# Power.net
KiCad netlist of a schematic drawn in Altium Designer
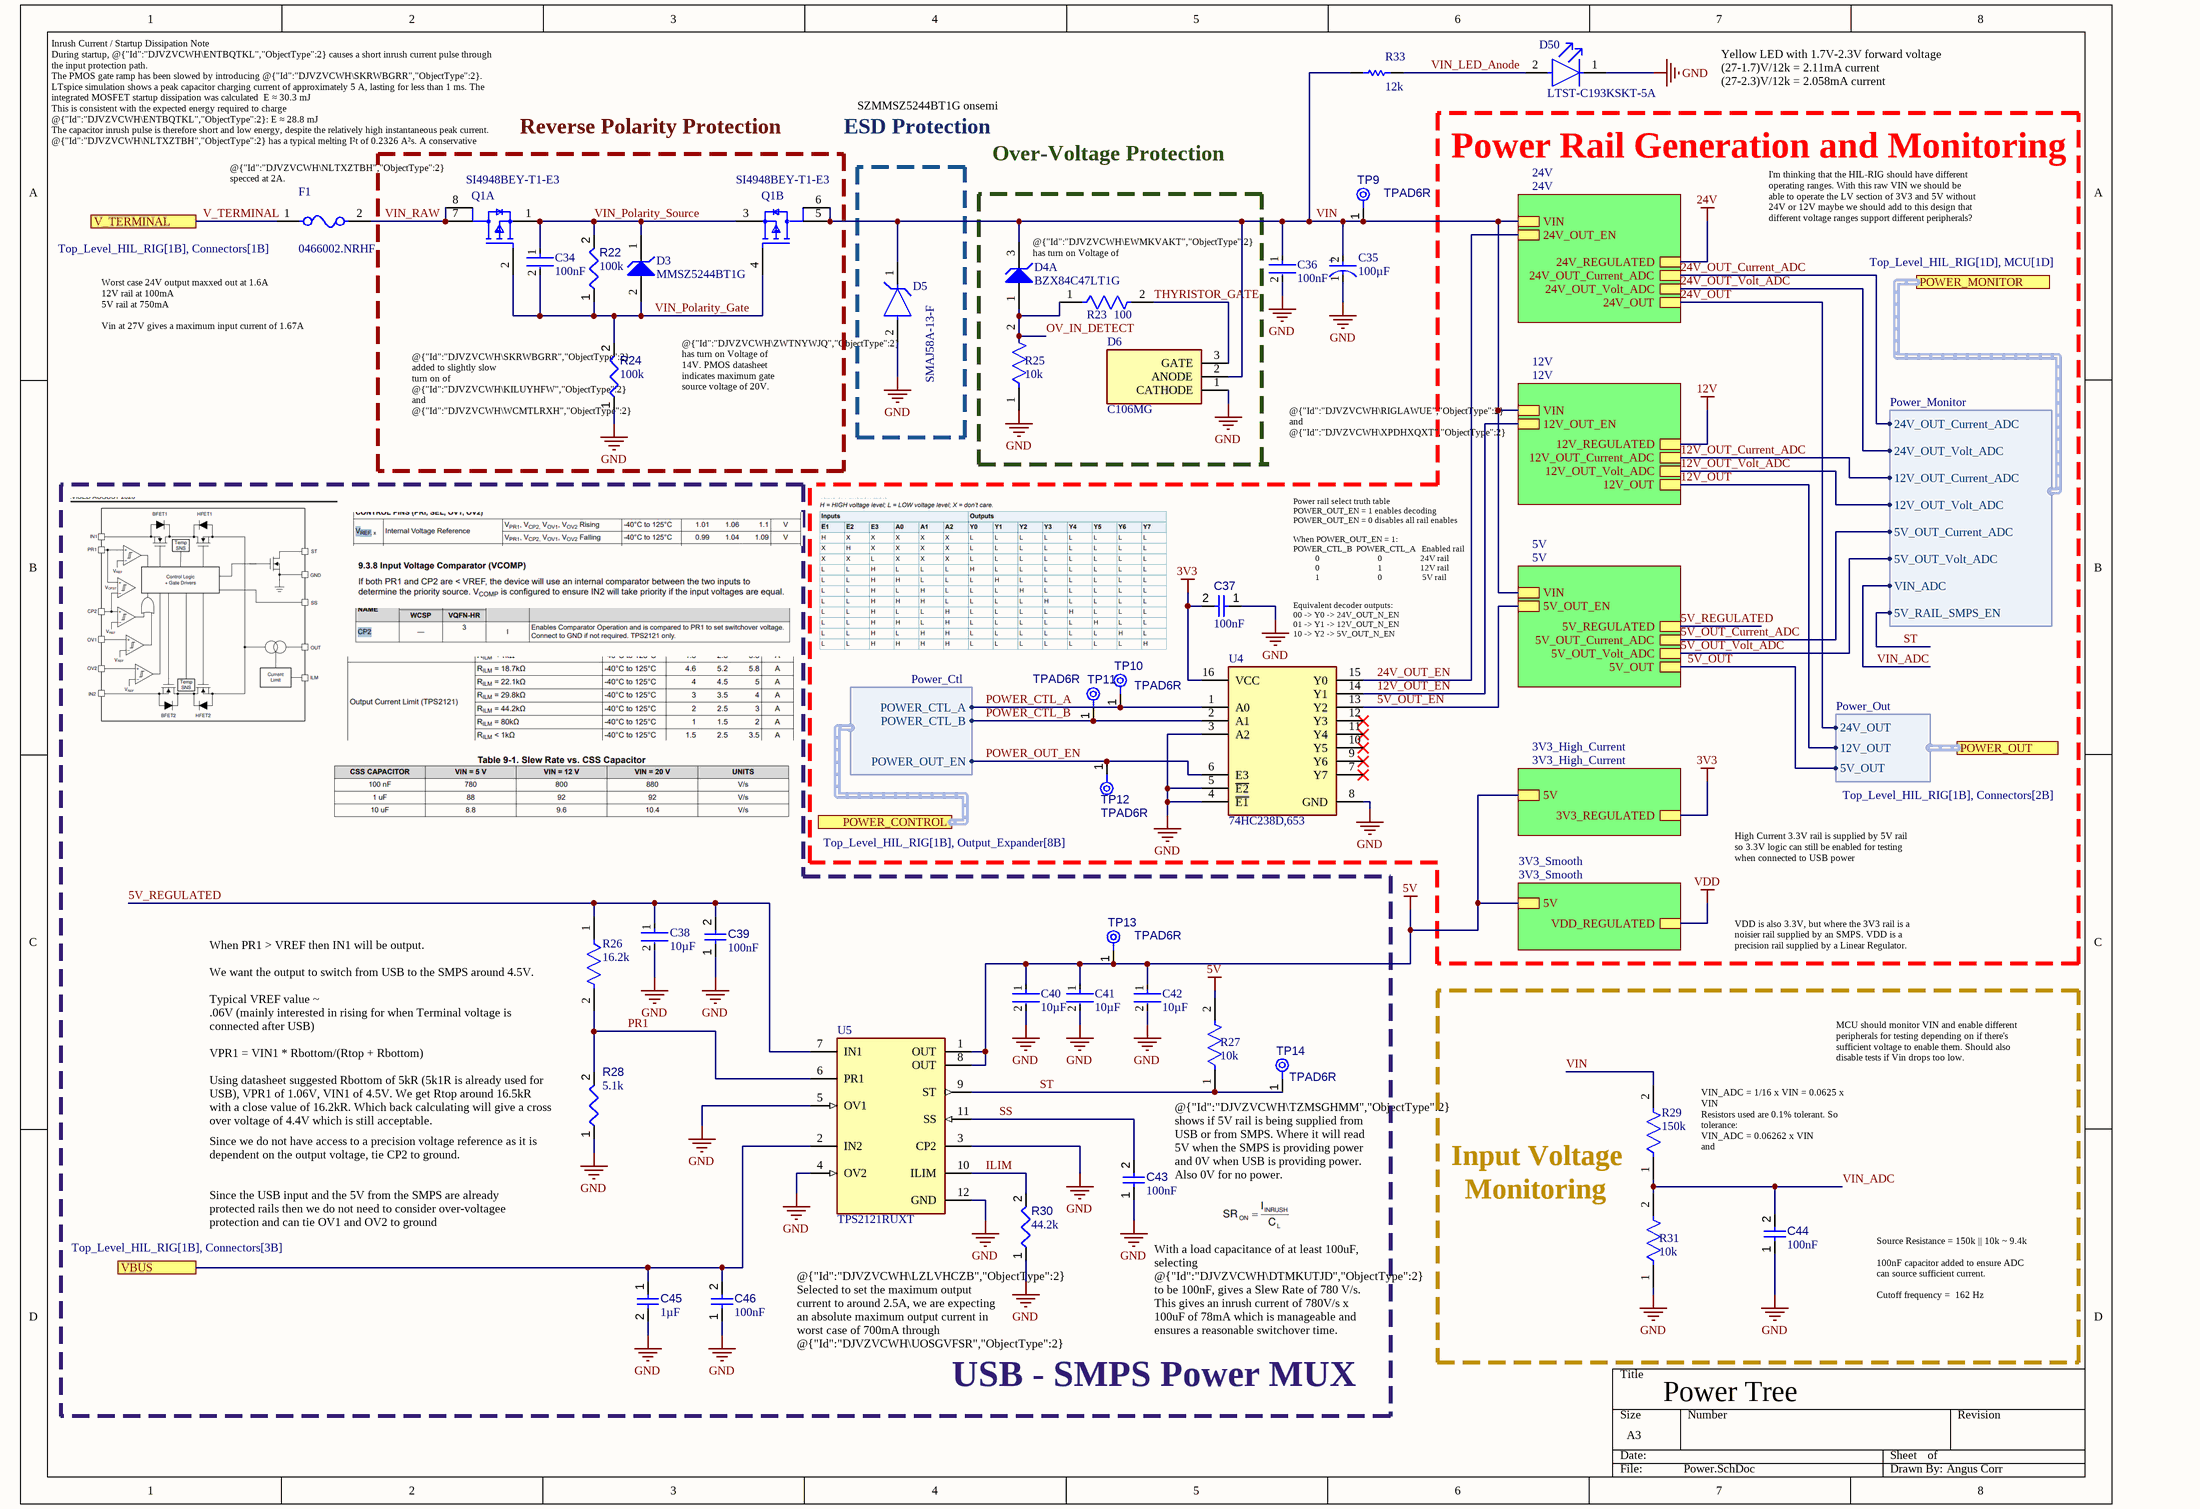
[diagram p0:  Power.SchDoc]

(export (version "E")
  (design (tool "Eeschema 10.0.6"))
  (components
    (comp (ref "C34")
      (value "100nF")
      (footprint "FP-GRM31C-0_2-e0_3_0_8-IPC_C")
      (description "100V 100nF C0G ±5% 1206 Multilayer Ceramic Capacitors MLCC - SMD/SMT ROHS")
      (fields (field (name "TOLERANCE") "5%") (field (name "Comment") "GRM31C5C2A104JA01L"))
      (libsource (lib "HIL RIG FYP") (part "02cd4be3c70576c341d710602a673aa"))
    )
    (comp (ref "C35")
      (value "100µF")
      (footprint "FP-MVYAKE0-MFG")
      (description "Cap Aluminum 100uF 100V 20% (12.5 X 13.5mm) SMD 450mA 5000h 105°C T/R")
      (fields (field (name "TOLERANCE") "20%") (field (name "Comment") "EMVY101ARA101MKE0S"))
      (libsource (lib "HIL RIG FYP") (part "203bc49f2ac43e59fd269a8c329ed05"))
    )
    (comp (ref "C36")
      (value "100nF")
      (footprint "FP-GRM31C-0_2-e0_3_0_8-IPC_C")
      (description "100V 100nF C0G ±5% 1206 Multilayer Ceramic Capacitors MLCC - SMD/SMT ROHS")
      (fields (field (name "TOLERANCE") "5%") (field (name "Comment") "GRM31C5C2A104JA01L"))
      (libsource (lib "HIL RIG FYP") (part "02cd4be3c70576c341d710602a673aa"))
    )
    (comp (ref "C37")
      (value "100nF")
      (footprint "CAPC1608X90X40NL10T20")
      (description "Chip Capacitor, 100 nF, +/- 10%, 50 V, 0603 (1608 Metric)")
      (fields (field (name "TOLERANCE") "10%") (field (name "Comment") "Capacitor 100 nF +/-10% 50 V 0603"))
      (libsource (lib "HIL RIG FYP") (part "CAP-NP-2"))
    )
    (comp (ref "C38")
      (value "10µF")
      (footprint "FP-GRM31C-0_2-e0_3_0_8-IPC_C")
      (description "25V 10uF X7R ±10% 1206 Multilayer Ceramic Capacitors MLCC - SMD/SMT ROHS")
      (fields (field (name "TOLERANCE") "10%") (field (name "VOLTAGE") "25V"))
      (libsource (lib "HIL RIG FYP") (part "02cd4be3c70576c341d710602a673aa"))
    )
    (comp (ref "C39")
      (value "100nF")
      (footprint "CAPC1608X90X40NL10T20")
      (description "Chip Capacitor, 100 nF, +/- 10%, 50 V, 0603 (1608 Metric)")
      (fields (field (name "TOLERANCE") "10%") (field (name "Comment") "Capacitor 100 nF +/-10% 50 V 0603"))
      (libsource (lib "HIL RIG FYP") (part "CAP-NP-2"))
    )
    (comp (ref "C40")
      (value "10µF")
      (footprint "FP-GRM31C-0_2-e0_3_0_8-IPC_C")
      (description "25V 10uF X7R ±10% 1206 Multilayer Ceramic Capacitors MLCC - SMD/SMT ROHS")
      (fields (field (name "TOLERANCE") "10%") (field (name "VOLTAGE") "25V"))
      (libsource (lib "HIL RIG FYP") (part "02cd4be3c70576c341d710602a673aa"))
    )
    (comp (ref "C41")
      (value "10µF")
      (footprint "FP-GRM31C-0_2-e0_3_0_8-IPC_C")
      (description "25V 10uF X7R ±10% 1206 Multilayer Ceramic Capacitors MLCC - SMD/SMT ROHS")
      (fields (field (name "TOLERANCE") "10%") (field (name "VOLTAGE") "25V"))
      (libsource (lib "HIL RIG FYP") (part "02cd4be3c70576c341d710602a673aa"))
    )
    (comp (ref "C42")
      (value "10µF")
      (footprint "FP-GRM31C-0_2-e0_3_0_8-IPC_C")
      (description "25V 10uF X7R ±10% 1206 Multilayer Ceramic Capacitors MLCC - SMD/SMT ROHS")
      (fields (field (name "TOLERANCE") "10%") (field (name "VOLTAGE") "25V"))
      (libsource (lib "HIL RIG FYP") (part "02cd4be3c70576c341d710602a673aa"))
    )
    (comp (ref "C43")
      (value "100nF")
      (footprint "CAPC1608X90X40NL10T20")
      (description "Chip Capacitor, 100 nF, +/- 10%, 50 V, 0603 (1608 Metric)")
      (fields (field (name "TOLERANCE") "10%") (field (name "Comment") "Capacitor 100 nF +/-10% 50 V 0603"))
      (libsource (lib "HIL RIG FYP") (part "CAP-NP-2"))
    )
    (comp (ref "C44")
      (value "100nF")
      (footprint "CAPC1608X90X40NL10T20")
      (description "Chip Capacitor, 100 nF, +/- 10%, 50 V, 0603 (1608 Metric)")
      (fields (field (name "TOLERANCE") "10%") (field (name "Comment") "Capacitor 100 nF +/-10% 50 V 0603"))
      (libsource (lib "HIL RIG FYP") (part "CAP-NP-2"))
    )
    (comp (ref "C45")
      (value "1µF")
      (footprint "CAPC1608X90X40LL10T20")
      (description "Chip Capacitor, 1 uF, +/- 10%, 25 V, 0603 (1608 Metric)")
      (fields (field (name "TOLERANCE") "10%") (field (name "Comment") "Capacitor 1 uF +/- 10% 25 V 0603"))
      (libsource (lib "HIL RIG FYP") (part "CAP-NP-2"))
    )
    (comp (ref "C46")
      (value "100nF")
      (footprint "CAPC1608X90X40NL10T20")
      (description "Chip Capacitor, 100 nF, +/- 10%, 50 V, 0603 (1608 Metric)")
      (fields (field (name "TOLERANCE") "10%") (field (name "Comment") "Capacitor 100 nF +/-10% 50 V 0603"))
      (libsource (lib "HIL RIG FYP") (part "CAP-NP-2"))
    )
    (comp (ref "D3")
      (value "MMSZ5244BT1G")
      (footprint "ONSC-SOD-123-2-425-04_V")
      (description "MMSZ5244BT1 Series 500 mW 10 mA 14 V SMT Zener Voltage Regulator - SOD-123")
      (fields (field (name "TOLERANCE") "5%"))
      (libsource (lib "HIL RIG FYP") (part "ONSC-K1A2-2"))
    )
    (comp (ref "D4")
      (value "BZX84C47LT1G")
      (footprint "ONSC-SOT-23-3-318-08_V")
      (description "Diode, Zener, Vr 47V, If 10MA, Pkg SOT-23 (TO-236), Vf 0.9V, Cj 40PF, Tj +150C, Ir 2MA")
      (libsource (lib "HIL RIG FYP") (part "ONSC-A1K3-3"))
    )
    (comp (ref "D5")
      (value "SMAJ58A-13-F")
      (footprint "FP-SMA-MFG")
      (description "SMAJ Series 58 V 400 W SMT Uni-Directional TVS Diode - DO-214AC")
      (libsource (lib "HIL RIG FYP") (part "f813f71cba58e380607f5dd3caf9714"))
    )
    (comp (ref "D6")
      (value "C106MG")
      (footprint "TO229P280X780X1410-3P")
      (description "Littelfuse")
      (fields (field (name "MOUSER PART NUMBER") "863-C106MG"))
      (libsource (lib "HIL RIG FYP") (part "C106MG"))
    )
    (comp (ref "D50")
      (value "LTST-C193KSKT-5A")
      (footprint "FP-LTST-C193KGKT-5A-MFG")
      (description "LED yellow 0603 wavelength 587~594.5nm light intensity 7.1~45mcd Front Mounting")
      (libsource (lib "HIL RIG FYP") (part "8706943c75ba83719d021d2fdc84c58"))
    )
    (comp (ref "F1")
      (value "0466002.NRHF")
      (footprint "FP-0466-MFG")
      (description "Fuse 63V Fa Halogen Free Slim 1206 2A/ T&r Rohs Compliant: Yes")
      (libsource (lib "HIL RIG FYP") (part "5bcf9b9f640e542cf0359d10258e979"))
    )
    (comp (ref "Q1")
      (value "SI4948BEY-T1-E3")
      (footprint "FP-C-06527-IPC_B")
      (description "Dual P-Channel 60 V 0.12 Ohms Surface Mount Power Mosfet - SOIC-8")
      (libsource (lib "HIL RIG FYP") (part "8dc75c867fb8938c255332086adbf49"))
    )
    (comp (ref "R22")
      (value "100k")
      (footprint "FP-AC0603-IPC_C")
      (description "Res Thick Film 0603 100K Ohm 1% 0.1W(1/10W) ±100ppm/C Pad SMD T/R Automotive")
      (fields (field (name "TOLERANCE") "1%") (field (name "Comment") "AC0603FR-07100KL"))
      (libsource (lib "HIL RIG FYP") (part "RES-2"))
    )
    (comp (ref "R23")
      (value "100")
      (footprint "FP-RT0603-IPC_C")
      (description "100mW Thin Film Resistor 75V ±25ppm/℃ ±0.1% 100Ω 0603 Chip Resistor - Surface Mount ROHS")
      (fields (field (name "TOLERANCE") "0.1%") (field (name "Comment") "RT0603BRD07100RL"))
      (libsource (lib "HIL RIG FYP") (part "1029c3af85768c4190bb7ad29bc67b5"))
    )
    (comp (ref "R24")
      (value "100k")
      (footprint "FP-AC0603-IPC_C")
      (description "Res Thick Film 0603 100K Ohm 1% 0.1W(1/10W) ±100ppm/C Pad SMD T/R Automotive")
      (fields (field (name "TOLERANCE") "1%") (field (name "Comment") "AC0603FR-07100KL"))
      (libsource (lib "HIL RIG FYP") (part "RES-2"))
    )
    (comp (ref "R25")
      (value "10k")
      (footprint "FP-RT0603-IPC_C")
      (description "Res Thin Film 0603 10K Ohm 0.1% 1/10W ¦25ppm/¦C SMD Paper T/R")
      (fields (field (name "TOLERANCE") "0.1%") (field (name "Comment") "RT0603BRD0710KL"))
      (libsource (lib "HIL RIG FYP") (part "1029c3af85768c4190bb7ad29bc67b5"))
    )
    (comp (ref "R26")
      (value "16.2k")
      (footprint "FP-RT0603-IPC_C")
      (description "100mW Thin Film Resistor ±25ppm/℃ ±0.1% 16.2kΩ 0603 Chip Resistor - Surface Mount ROHS")
      (fields (field (name "TOLERANCE") "0.1%") (field (name "Comment") "RT0603BRD0716K2L"))
      (libsource (lib "HIL RIG FYP") (part "1029c3af85768c4190bb7ad29bc67b5"))
    )
    (comp (ref "R27")
      (value "10k")
      (footprint "FP-RT0603-IPC_C")
      (description "Res Thin Film 0603 10K Ohm 0.1% 1/10W ¦25ppm/¦C SMD Paper T/R")
      (fields (field (name "TOLERANCE") "0.1%") (field (name "Comment") "RT0603BRD0710KL"))
      (libsource (lib "HIL RIG FYP") (part "1029c3af85768c4190bb7ad29bc67b5"))
    )
    (comp (ref "R28")
      (value "5.1k")
      (footprint "FP-AC0603-IPC_C")
      (description "Res Thick Film 0603 5.1K Ohm 1% 0.1W(1/10W) ±100ppm/C Pad SMD Automotive T/R")
      (fields (field (name "TOLERANCE") "1%") (field (name "Comment") "AC0603FR-075K1L"))
      (libsource (lib "HIL RIG FYP") (part "RES-2"))
    )
    (comp (ref "R29")
      (value "150k")
      (footprint "FP-RT0805-MFG")
      (description "125mW Thin Film Resistor 150V ±25ppm/℃ ±0.1% 150kΩ 0805 Chip Resistor - Surface Mount ROHS")
      (fields (field (name "TOLERANCE") "0.1%") (field (name "Comment") "RT0805BRD07150KL"))
      (libsource (lib "HIL RIG FYP") (part "1029c3af85768c4190bb7ad29bc67b5"))
    )
    (comp (ref "R30")
      (value "44.2k")
      (footprint "FP-AC0603-IPC_C")
      (description "Res Thick Film 0603 44.2K Ohm 1% 0.1W(1/10W) ±100ppm/C Pad SMD T/R Automotive AEC-Q200")
      (fields (field (name "TOLERANCE") "1%") (field (name "Comment") "AC0603FR-0744K2L"))
      (libsource (lib "HIL RIG FYP") (part "RES-2"))
    )
    (comp (ref "R31")
      (value "10k")
      (footprint "FP-RT0603-IPC_C")
      (description "Res Thin Film 0603 10K Ohm 0.1% 1/10W ¦25ppm/¦C SMD Paper T/R")
      (fields (field (name "TOLERANCE") "0.1%") (field (name "Comment") "RT0603BRD0710KL"))
      (libsource (lib "HIL RIG FYP") (part "1029c3af85768c4190bb7ad29bc67b5"))
    )
    (comp (ref "R33")
      (value "12k")
      (footprint "RESC1608X55X25LL10T15")
      (description "100mW Thick Film Resistors 75V ±100ppm/℃ ±1% 12kΩ 0603 Chip Resistor - Surface Mount ROHS")
      (fields (field (name "TOLERANCE") "1%") (field (name "Comment") "RC0603FR-0712KL"))
      (libsource (lib "") (part "RES-2_1"))
    )
    (comp (ref "TP9")
      (value "TPAD6R")
      (footprint "TP06R")
      (description "0.6mm round")
      (libsource (lib "HIL RIG FYP") (part "CMP-001-0001-4"))
    )
    (comp (ref "TP10")
      (value "TPAD6R")
      (footprint "TP06R")
      (description "0.6mm round")
      (libsource (lib "HIL RIG FYP") (part "CMP-001-0001-4"))
    )
    (comp (ref "TP11")
      (value "TPAD6R")
      (footprint "TP06R")
      (description "0.6mm round")
      (libsource (lib "HIL RIG FYP") (part "CMP-001-0001-4"))
    )
    (comp (ref "TP12")
      (value "TPAD6R")
      (footprint "TP06R")
      (description "0.6mm round")
      (libsource (lib "HIL RIG FYP") (part "CMP-001-0001-4"))
    )
    (comp (ref "TP13")
      (value "TPAD6R")
      (footprint "TP06R")
      (description "0.6mm round")
      (libsource (lib "HIL RIG FYP") (part "CMP-001-0001-4"))
    )
    (comp (ref "TP14")
      (value "TPAD6R")
      (footprint "TP06R")
      (description "0.6mm round")
      (libsource (lib "HIL RIG FYP") (part "CMP-001-0001-4"))
    )
    (comp (ref "U4")
      (value "74HC238D,653")
      (footprint "74HC238D653")
      (description "74HC(T)238 - 3-to-8 line decoder/demultiplexer@en-us")
      (fields (field (name "MOUSER PART NUMBER") "771-74HC238D-T"))
      (libsource (lib "HIL RIG FYP") (part "74HC238D,653"))
    )
    (comp (ref "U5")
      (value "TPS2121RUXT")
      (footprint "FP-RUX0012A-MFG")
      (description "2.7-V to 22-V, 56-mΩ, 4.5-A, power mux with seamless switchover 12-VQFN-HR -40 to 125")
      (libsource (lib "HIL RIG FYP") (part "f7eeb2b54b908798336ebc03d3325e5"))
    )
  )
  (nets
    (net (code "6") (name "/5V_OUT_EN") (class "Default")
      (node (ref "U4") (pin "13") (pinfunction "Y2_13") (pintype "passive"))
    )
    (net (code "8") (name "/5V_REGULATED") (class "Default")
      (node (ref "C38") (pin "1") (pinfunction "1_1") (pintype "passive"))
      (node (ref "C39") (pin "2") (pinfunction "2_2") (pintype "passive"))
      (node (ref "R26") (pin "1") (pinfunction "1_1") (pintype "passive"))
      (node (ref "U5") (pin "7") (pinfunction "IN1_7") (pintype "power_in"))
    )
    (net (code "11") (name "/12V_OUT_EN") (class "Default")
      (node (ref "U4") (pin "14") (pinfunction "Y1_14") (pintype "passive"))
    )
    (net (code "15") (name "/24V_OUT_EN") (class "Default")
      (node (ref "U4") (pin "15") (pinfunction "Y0_15") (pintype "passive"))
    )
    (net (code "17") (name "/ILIM") (class "Default")
      (node (ref "R30") (pin "2") (pinfunction "2_2") (pintype "passive"))
      (node (ref "U5") (pin "10") (pinfunction "ILIM_10") (pintype "passive"))
    )
    (net (code "18") (name "/OV_IN_DETECT") (class "Default")
      (node (ref "D4") (pin "1") (pinfunction "A_1") (pintype "passive"))
      (node (ref "R23") (pin "1") (pinfunction "1_1") (pintype "passive"))
      (node (ref "R25") (pin "2") (pinfunction "2_2") (pintype "passive"))
    )
    (net (code "19") (name "/POWER_CTL_A") (class "Default")
      (node (ref "TP10") (pin "1") (pinfunction "TP_1") (pintype "passive"))
      (node (ref "U4") (pin "1") (pinfunction "A0_1") (pintype "passive"))
    )
    (net (code "20") (name "/POWER_CTL_B") (class "Default")
      (node (ref "TP11") (pin "1") (pinfunction "TP_1") (pintype "passive"))
      (node (ref "U4") (pin "2") (pinfunction "A1_2") (pintype "passive"))
    )
    (net (code "21") (name "/POWER_OUT_EN") (class "Default")
      (node (ref "TP12") (pin "1") (pinfunction "TP_1") (pintype "passive"))
      (node (ref "U4") (pin "6") (pinfunction "E3_6") (pintype "passive"))
    )
    (net (code "22") (name "/PR1") (class "Default")
      (node (ref "R26") (pin "2") (pinfunction "2_2") (pintype "passive"))
      (node (ref "R28") (pin "2") (pinfunction "2_2") (pintype "passive"))
      (node (ref "U5") (pin "6") (pinfunction "PR1_6") (pintype "passive"))
    )
    (net (code "23") (name "/SS") (class "Default")
      (node (ref "C43") (pin "2") (pinfunction "2_2") (pintype "passive"))
      (node (ref "U5") (pin "11") (pinfunction "SS_11") (pintype "input"))
    )
    (net (code "24") (name "/ST") (class "Default")
      (node (ref "R27") (pin "1") (pinfunction "1_1") (pintype "passive"))
      (node (ref "TP14") (pin "1") (pinfunction "TP_1") (pintype "passive"))
      (node (ref "U5") (pin "9") (pinfunction "ST_9") (pintype "output"))
    )
    (net (code "25") (name "/THYRISTOR_GATE") (class "Default")
      (node (ref "D6") (pin "3") (pinfunction "GATE_3") (pintype "passive"))
      (node (ref "R23") (pin "2") (pinfunction "2_2") (pintype "passive"))
    )
    (net (code "26") (name "/VBUS") (class "Default")
      (node (ref "C45") (pin "1") (pinfunction "1_1") (pintype "passive"))
      (node (ref "C46") (pin "2") (pinfunction "2_2") (pintype "passive"))
      (node (ref "U5") (pin "2") (pinfunction "IN2_2") (pintype "power_in"))
    )
    (net (code "27") (name "/VIN") (class "Default")
      (node (ref "C35") (pin "2") (pinfunction "A_2") (pintype "passive"))
      (node (ref "C36") (pin "1") (pinfunction "1_1") (pintype "passive"))
      (node (ref "D4") (pin "3") (pinfunction "K_3") (pintype "passive"))
      (node (ref "D5") (pin "1") (pinfunction "C_1") (pintype "passive"))
      (node (ref "D6") (pin "2") (pinfunction "ANODE_2") (pintype "passive"))
      (node (ref "Q1") (pin "5") (pinfunction "D2_5") (pintype "passive"))
      (node (ref "Q1") (pin "6") (pinfunction "D2_6") (pintype "passive"))
      (node (ref "R29") (pin "2") (pinfunction "2_2") (pintype "passive"))
      (node (ref "R33") (pin "1") (pinfunction "1_1") (pintype "passive"))
      (node (ref "TP9") (pin "1") (pinfunction "TP_1") (pintype "passive"))
    )
    (net (code "28") (name "/VIN_ADC") (class "Default")
      (node (ref "C44") (pin "2") (pinfunction "2_2") (pintype "passive"))
      (node (ref "R29") (pin "1") (pinfunction "1_1") (pintype "passive"))
      (node (ref "R31") (pin "2") (pinfunction "2_2") (pintype "passive"))
    )
    (net (code "29") (name "/VIN_LED_Anode") (class "Default")
      (node (ref "D50") (pin "2") (pinfunction "A_2") (pintype "passive"))
      (node (ref "R33") (pin "2") (pinfunction "2_2") (pintype "passive"))
    )
    (net (code "30") (name "/VIN_Polarity_Gate") (class "Default")
      (node (ref "C34") (pin "2") (pinfunction "2_2") (pintype "passive"))
      (node (ref "D3") (pin "2") (pinfunction "A_2") (pintype "passive"))
      (node (ref "Q1") (pin "2") (pinfunction "G1_2") (pintype "passive"))
      (node (ref "Q1") (pin "4") (pinfunction "G2_4") (pintype "passive"))
      (node (ref "R22") (pin "1") (pinfunction "1_1") (pintype "passive"))
      (node (ref "R24") (pin "2") (pinfunction "2_2") (pintype "passive"))
    )
    (net (code "31") (name "/VIN_Polarity_Source") (class "Default")
      (node (ref "C34") (pin "1") (pinfunction "1_1") (pintype "passive"))
      (node (ref "D3") (pin "1") (pinfunction "K_1") (pintype "passive"))
      (node (ref "Q1") (pin "1") (pinfunction "S1_1") (pintype "passive"))
      (node (ref "Q1") (pin "3") (pinfunction "S2_3") (pintype "passive"))
      (node (ref "R22") (pin "2") (pinfunction "2_2") (pintype "passive"))
    )
    (net (code "32") (name "/VIN_RAW") (class "Default")
      (node (ref "F1") (pin "2") (pinfunction "2_2") (pintype "passive"))
      (node (ref "Q1") (pin "7") (pinfunction "D1_7") (pintype "passive"))
      (node (ref "Q1") (pin "8") (pinfunction "D1_8") (pintype "passive"))
    )
    (net (code "33") (name "/V_TERMINAL") (class "Default")
      (node (ref "F1") (pin "1") (pinfunction "1_1") (pintype "passive"))
    )
    (net (code "37") (name "3V3") (class "Default")
      (node (ref "C37") (pin "2") (pinfunction "2_2") (pintype "passive"))
      (node (ref "U4") (pin "16") (pinfunction "VCC_16") (pintype "passive"))
    )
    (net (code "38") (name "5V") (class "Default")
      (node (ref "C40") (pin "1") (pinfunction "1_1") (pintype "passive"))
      (node (ref "C41") (pin "1") (pinfunction "1_1") (pintype "passive"))
      (node (ref "C42") (pin "1") (pinfunction "1_1") (pintype "passive"))
      (node (ref "R27") (pin "2") (pinfunction "2_2") (pintype "passive"))
      (node (ref "TP13") (pin "1") (pinfunction "TP_1") (pintype "passive"))
      (node (ref "U5") (pin "1") (pinfunction "OUT_1") (pintype "power_in"))
      (node (ref "U5") (pin "8") (pinfunction "OUT_8") (pintype "passive"))
    )
    (net (code "41") (name "GND") (class "Default")
      (node (ref "C35") (pin "1") (pinfunction "C_1") (pintype "passive"))
      (node (ref "C36") (pin "2") (pinfunction "2_2") (pintype "passive"))
      (node (ref "C37") (pin "1") (pinfunction "1_1") (pintype "passive"))
      (node (ref "C38") (pin "2") (pinfunction "2_2") (pintype "passive"))
      (node (ref "C39") (pin "1") (pinfunction "1_1") (pintype "passive"))
      (node (ref "C40") (pin "2") (pinfunction "2_2") (pintype "passive"))
      (node (ref "C41") (pin "2") (pinfunction "2_2") (pintype "passive"))
      (node (ref "C42") (pin "2") (pinfunction "2_2") (pintype "passive"))
      (node (ref "C43") (pin "1") (pinfunction "1_1") (pintype "passive"))
      (node (ref "C44") (pin "1") (pinfunction "1_1") (pintype "passive"))
      (node (ref "C45") (pin "2") (pinfunction "2_2") (pintype "passive"))
      (node (ref "C46") (pin "1") (pinfunction "1_1") (pintype "passive"))
      (node (ref "D5") (pin "2") (pinfunction "A_2") (pintype "passive"))
      (node (ref "D50") (pin "1") (pinfunction "C_1") (pintype "passive"))
      (node (ref "D6") (pin "1") (pinfunction "CATHODE_1") (pintype "passive"))
      (node (ref "R24") (pin "1") (pinfunction "1_1") (pintype "passive"))
      (node (ref "R25") (pin "1") (pinfunction "1_1") (pintype "passive"))
      (node (ref "R28") (pin "1") (pinfunction "1_1") (pintype "passive"))
      (node (ref "R30") (pin "1") (pinfunction "1_1") (pintype "passive"))
      (node (ref "R31") (pin "1") (pinfunction "1_1") (pintype "passive"))
      (node (ref "U4") (pin "3") (pinfunction "A2_3") (pintype "passive"))
      (node (ref "U4") (pin "4") (pinfunction "~{E1}_4") (pintype "passive"))
      (node (ref "U4") (pin "5") (pinfunction "~{E2}_5") (pintype "passive"))
      (node (ref "U4") (pin "8") (pinfunction "GND_8") (pintype "passive"))
      (node (ref "U5") (pin "12") (pinfunction "GND_12") (pintype "power_in"))
      (node (ref "U5") (pin "3") (pinfunction "CP2_3") (pintype "passive"))
      (node (ref "U5") (pin "4") (pinfunction "OV2_4") (pintype "input"))
      (node (ref "U5") (pin "5") (pinfunction "OV1_5") (pintype "input"))
    )
    (net (code "43") (name "unconnected-(U4-Y3-Pad12)") (class "Default")
      (node (ref "U4") (pin "12") (pinfunction "Y3_12") (pintype "passive+no_connect"))
    )
    (net (code "44") (name "unconnected-(U4-Y4-Pad11)") (class "Default")
      (node (ref "U4") (pin "11") (pinfunction "Y4_11") (pintype "passive+no_connect"))
    )
    (net (code "45") (name "unconnected-(U4-Y5-Pad10)") (class "Default")
      (node (ref "U4") (pin "10") (pinfunction "Y5_10") (pintype "passive+no_connect"))
    )
    (net (code "46") (name "unconnected-(U4-Y6-Pad9)") (class "Default")
      (node (ref "U4") (pin "9") (pinfunction "Y6_9") (pintype "passive+no_connect"))
    )
    (net (code "47") (name "unconnected-(U4-Y7-Pad7)") (class "Default")
      (node (ref "U4") (pin "7") (pinfunction "Y7_7") (pintype "passive+no_connect"))
    )
  )
)
